# brakelight.net
KiCad netlist of a schematic drawn in Altium Designer
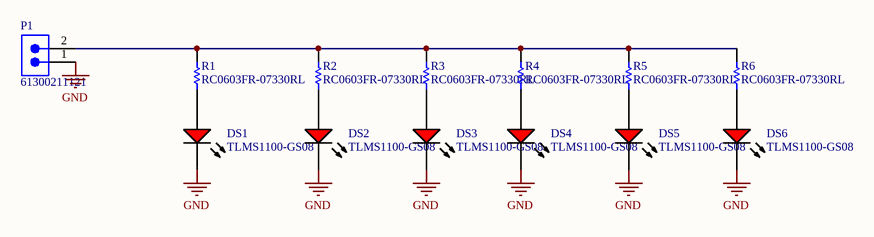
[diagram p0: brakelight.SchDoc]

(export (version "E")
  (design (tool "Eeschema 10.0.6"))
  (components
    (comp (ref "DS1")
      (value "TLMS1100-GS08")
      (footprint "VISH-TLMX1100_V")
      (description "LED, RED, 2.1 V, -40 to 100 degC, 2-Pin SMD (0603), RoHS, Tape and Reel")
      (fields (field (name "TOLERANCE") "5%"))
      (libsource (lib "Altium Content Vault") (part "LED-RED-AK-2"))
    )
    (comp (ref "DS2")
      (value "TLMS1100-GS08")
      (footprint "VISH-TLMX1100_V")
      (description "LED, RED, 2.1 V, -40 to 100 degC, 2-Pin SMD (0603), RoHS, Tape and Reel")
      (fields (field (name "TOLERANCE") "5%"))
      (libsource (lib "Altium Content Vault") (part "LED-RED-AK-2"))
    )
    (comp (ref "DS3")
      (value "TLMS1100-GS08")
      (footprint "VISH-TLMX1100_V")
      (description "LED, RED, 2.1 V, -40 to 100 degC, 2-Pin SMD (0603), RoHS, Tape and Reel")
      (fields (field (name "TOLERANCE") "5%"))
      (libsource (lib "Altium Content Vault") (part "LED-RED-AK-2"))
    )
    (comp (ref "DS4")
      (value "TLMS1100-GS08")
      (footprint "VISH-TLMX1100_V")
      (description "LED, RED, 2.1 V, -40 to 100 degC, 2-Pin SMD (0603), RoHS, Tape and Reel")
      (fields (field (name "TOLERANCE") "5%"))
      (libsource (lib "Altium Content Vault") (part "LED-RED-AK-2"))
    )
    (comp (ref "DS5")
      (value "TLMS1100-GS08")
      (footprint "VISH-TLMX1100_V")
      (description "LED, RED, 2.1 V, -40 to 100 degC, 2-Pin SMD (0603), RoHS, Tape and Reel")
      (fields (field (name "TOLERANCE") "5%"))
      (libsource (lib "Altium Content Vault") (part "LED-RED-AK-2"))
    )
    (comp (ref "DS6")
      (value "TLMS1100-GS08")
      (footprint "VISH-TLMX1100_V")
      (description "LED, RED, 2.1 V, -40 to 100 degC, 2-Pin SMD (0603), RoHS, Tape and Reel")
      (fields (field (name "TOLERANCE") "5%"))
      (libsource (lib "Altium Content Vault") (part "LED-RED-AK-2"))
    )
    (comp (ref "P1")
      (value "61300211121")
      (footprint "61300211121")
      (libsource (lib "Altium Content Vault") (part "Header_Male_1R_02P"))
    )
    (comp (ref "R1")
      (value "RC0603FR-07330RL")
      (footprint "RESC1608X55X25NL10T15")
      (description "Chip Resistor, 330 Ohm, +/- 1%, 0.1 W, -55 to 155 degC, 0603 (1608 Metric), RoHS, Tape and Reel")
      (fields (field (name "TOLERANCE") "10%"))
      (libsource (lib "Altium Content Vault") (part "RES-2"))
    )
    (comp (ref "R2")
      (value "RC0603FR-07330RL")
      (footprint "RESC1608X55X25NL10T15")
      (description "Chip Resistor, 330 Ohm, +/- 1%, 0.1 W, -55 to 155 degC, 0603 (1608 Metric), RoHS, Tape and Reel")
      (fields (field (name "TOLERANCE") "10%"))
      (libsource (lib "Altium Content Vault") (part "RES-2"))
    )
    (comp (ref "R3")
      (value "RC0603FR-07330RL")
      (footprint "RESC1608X55X25NL10T15")
      (description "Chip Resistor, 330 Ohm, +/- 1%, 0.1 W, -55 to 155 degC, 0603 (1608 Metric), RoHS, Tape and Reel")
      (fields (field (name "TOLERANCE") "10%"))
      (libsource (lib "Altium Content Vault") (part "RES-2"))
    )
    (comp (ref "R4")
      (value "RC0603FR-07330RL")
      (footprint "RESC1608X55X25NL10T15")
      (description "Chip Resistor, 330 Ohm, +/- 1%, 0.1 W, -55 to 155 degC, 0603 (1608 Metric), RoHS, Tape and Reel")
      (fields (field (name "TOLERANCE") "10%"))
      (libsource (lib "Altium Content Vault") (part "RES-2"))
    )
    (comp (ref "R5")
      (value "RC0603FR-07330RL")
      (footprint "RESC1608X55X25NL10T15")
      (description "Chip Resistor, 330 Ohm, +/- 1%, 0.1 W, -55 to 155 degC, 0603 (1608 Metric), RoHS, Tape and Reel")
      (fields (field (name "TOLERANCE") "10%"))
      (libsource (lib "Altium Content Vault") (part "RES-2"))
    )
    (comp (ref "R6")
      (value "RC0603FR-07330RL")
      (footprint "RESC1608X55X25NL10T15")
      (description "Chip Resistor, 330 Ohm, +/- 1%, 0.1 W, -55 to 155 degC, 0603 (1608 Metric), RoHS, Tape and Reel")
      (fields (field (name "TOLERANCE") "10%"))
      (libsource (lib "Altium Content Vault") (part "RES-2"))
    )
  )
  (nets
    (net (code "1") (name "GND") (class "Default")
      (node (ref "DS1") (pin "2") (pinfunction "K_2") (pintype "passive"))
      (node (ref "DS2") (pin "2") (pinfunction "K_2") (pintype "passive"))
      (node (ref "DS3") (pin "2") (pinfunction "K_2") (pintype "passive"))
      (node (ref "DS4") (pin "2") (pinfunction "K_2") (pintype "passive"))
      (node (ref "DS5") (pin "2") (pinfunction "K_2") (pintype "passive"))
      (node (ref "DS6") (pin "2") (pinfunction "K_2") (pintype "passive"))
      (node (ref "P1") (pin "1") (pinfunction "1_1") (pintype "passive"))
    )
    (net (code "2") (name "Net-(DS1-A)") (class "Default")
      (node (ref "DS1") (pin "1") (pinfunction "A_1") (pintype "passive"))
      (node (ref "R1") (pin "1") (pinfunction "1_1") (pintype "passive"))
    )
    (net (code "3") (name "Net-(DS2-A)") (class "Default")
      (node (ref "DS2") (pin "1") (pinfunction "A_1") (pintype "passive"))
      (node (ref "R2") (pin "1") (pinfunction "1_1") (pintype "passive"))
    )
    (net (code "4") (name "Net-(DS3-A)") (class "Default")
      (node (ref "DS3") (pin "1") (pinfunction "A_1") (pintype "passive"))
      (node (ref "R3") (pin "1") (pinfunction "1_1") (pintype "passive"))
    )
    (net (code "5") (name "Net-(DS4-A)") (class "Default")
      (node (ref "DS4") (pin "1") (pinfunction "A_1") (pintype "passive"))
      (node (ref "R4") (pin "1") (pinfunction "1_1") (pintype "passive"))
    )
    (net (code "6") (name "Net-(DS5-A)") (class "Default")
      (node (ref "DS5") (pin "1") (pinfunction "A_1") (pintype "passive"))
      (node (ref "R5") (pin "1") (pinfunction "1_1") (pintype "passive"))
    )
    (net (code "7") (name "Net-(DS6-A)") (class "Default")
      (node (ref "DS6") (pin "1") (pinfunction "A_1") (pintype "passive"))
      (node (ref "R6") (pin "1") (pinfunction "1_1") (pintype "passive"))
    )
    (net (code "8") (name "Net-(P1-Pad2)") (class "Default")
      (node (ref "P1") (pin "2") (pinfunction "2_2") (pintype "passive"))
      (node (ref "R1") (pin "2") (pinfunction "2_2") (pintype "passive"))
      (node (ref "R2") (pin "2") (pinfunction "2_2") (pintype "passive"))
      (node (ref "R3") (pin "2") (pinfunction "2_2") (pintype "passive"))
      (node (ref "R4") (pin "2") (pinfunction "2_2") (pintype "passive"))
      (node (ref "R5") (pin "2") (pinfunction "2_2") (pintype "passive"))
      (node (ref "R6") (pin "2") (pinfunction "2_2") (pintype "passive"))
    )
  )
)
